# interfaces.net
KiCad netlist of a schematic drawn in Altium Designer
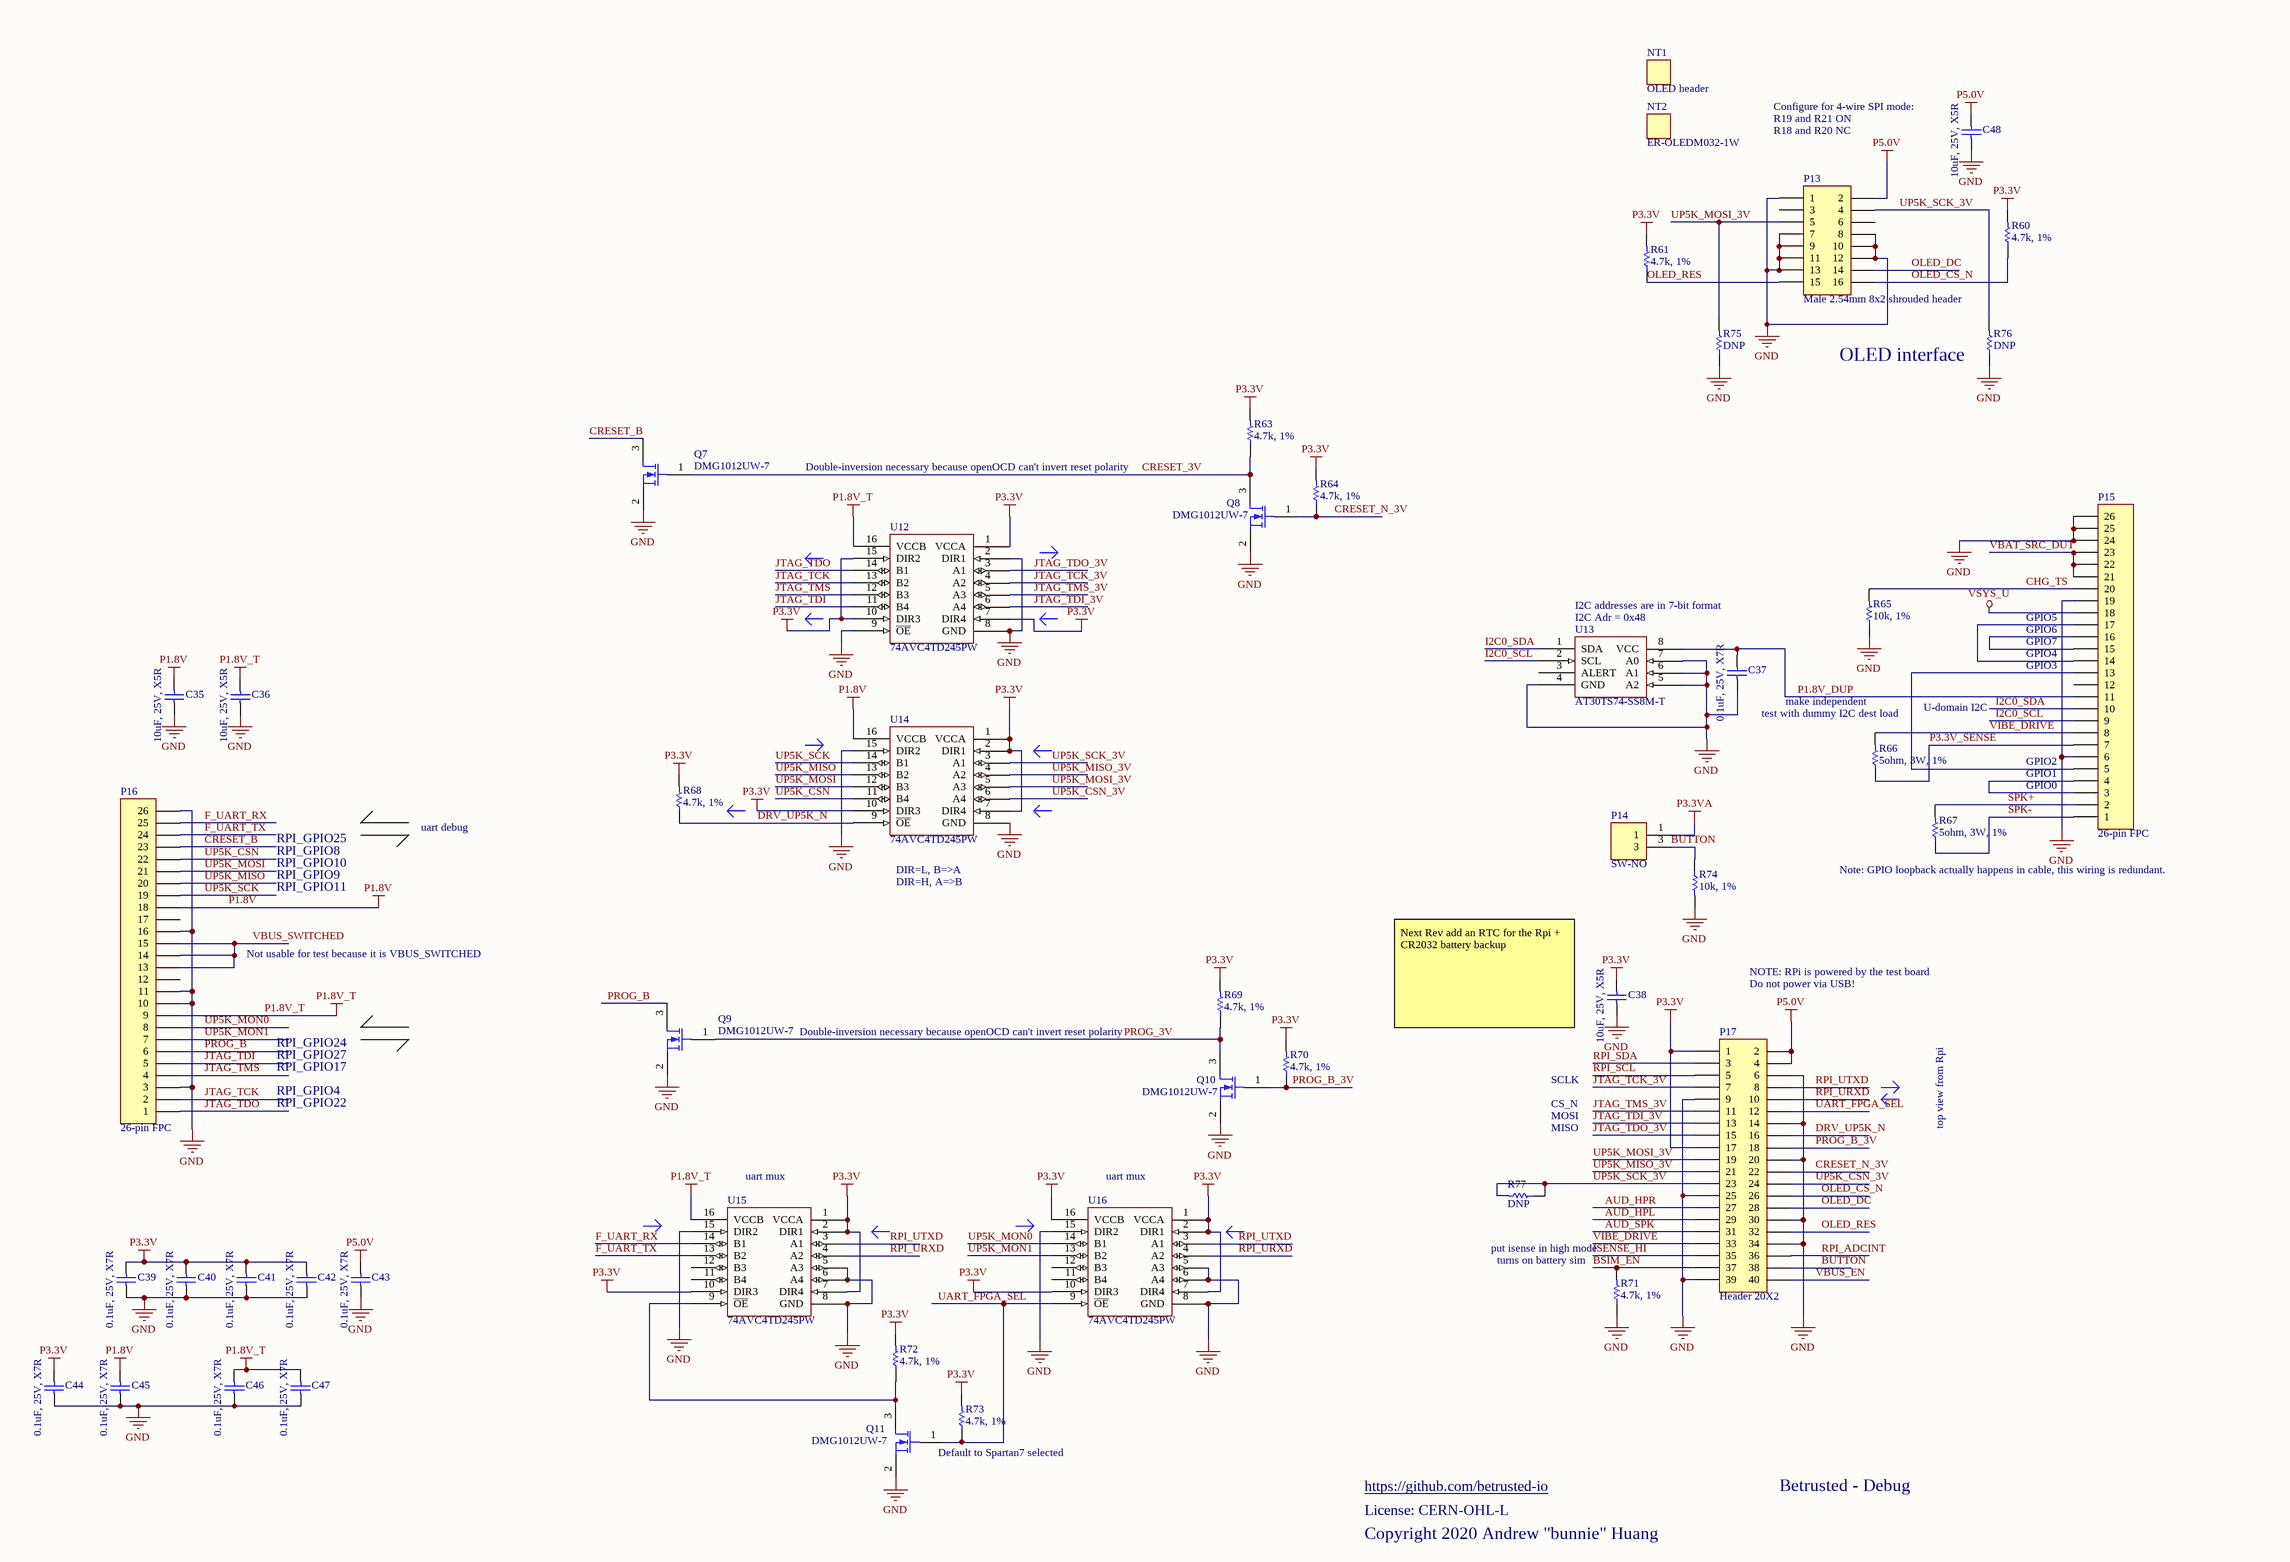
[diagram p0: interfaces.SchDoc]

(export (version "E")
  (design (tool "Eeschema 10.0.6"))
  (components
    (comp (ref "C35")
      (value "10uF, 25V, X5R")
      (footprint "B_CAP0805")
      (description "Capacitor (Semiconductor SIM Model)")
      (fields (field (name "MPN") "GRM21BR61E106KA73L"))
      (libsource (lib "Miscellaneous Devices") (part "Cap Semi"))
    )
    (comp (ref "C36")
      (value "10uF, 25V, X5R")
      (footprint "B_CAP0805")
      (description "Capacitor (Semiconductor SIM Model)")
      (fields (field (name "MPN") "GRM21BR61E106KA73L"))
      (libsource (lib "Miscellaneous Devices") (part "Cap Semi"))
    )
    (comp (ref "C37")
      (value "0.1uF, 25V, X7R")
      (footprint "B_CAP0603")
      (description "Capacitor (Semiconductor SIM Model)")
      (fields (field (name "MPN") "CC0603KRX7R8BB104"))
      (libsource (lib "Miscellaneous Devices") (part "Cap Semi"))
    )
    (comp (ref "C38")
      (value "10uF, 25V, X5R")
      (footprint "B_CAP0805")
      (description "Capacitor (Semiconductor SIM Model)")
      (fields (field (name "MPN") "GRM21BR61E106KA73L"))
      (libsource (lib "Miscellaneous Devices") (part "Cap Semi"))
    )
    (comp (ref "C39")
      (value "0.1uF, 25V, X7R")
      (footprint "B_CAP0603")
      (description "Capacitor (Semiconductor SIM Model)")
      (fields (field (name "MPN") "CC0603KRX7R8BB104"))
      (libsource (lib "Miscellaneous Devices") (part "Cap Semi"))
    )
    (comp (ref "C40")
      (value "0.1uF, 25V, X7R")
      (footprint "B_CAP0603")
      (description "Capacitor (Semiconductor SIM Model)")
      (fields (field (name "MPN") "CC0603KRX7R8BB104"))
      (libsource (lib "Miscellaneous Devices") (part "Cap Semi"))
    )
    (comp (ref "C41")
      (value "0.1uF, 25V, X7R")
      (footprint "B_CAP0603")
      (description "Capacitor (Semiconductor SIM Model)")
      (fields (field (name "MPN") "CC0603KRX7R8BB104"))
      (libsource (lib "Miscellaneous Devices") (part "Cap Semi"))
    )
    (comp (ref "C42")
      (value "0.1uF, 25V, X7R")
      (footprint "B_CAP0603")
      (description "Capacitor (Semiconductor SIM Model)")
      (fields (field (name "MPN") "CC0603KRX7R8BB104"))
      (libsource (lib "Miscellaneous Devices") (part "Cap Semi"))
    )
    (comp (ref "C43")
      (value "0.1uF, 25V, X7R")
      (footprint "B_CAP0603")
      (description "Capacitor (Semiconductor SIM Model)")
      (fields (field (name "MPN") "CC0603KRX7R8BB104"))
      (libsource (lib "Miscellaneous Devices") (part "Cap Semi"))
    )
    (comp (ref "C44")
      (value "0.1uF, 25V, X7R")
      (footprint "B_CAP0603")
      (description "Capacitor (Semiconductor SIM Model)")
      (fields (field (name "MPN") "CC0603KRX7R8BB104"))
      (libsource (lib "Miscellaneous Devices") (part "Cap Semi"))
    )
    (comp (ref "C45")
      (value "0.1uF, 25V, X7R")
      (footprint "B_CAP0603")
      (description "Capacitor (Semiconductor SIM Model)")
      (fields (field (name "MPN") "CC0603KRX7R8BB104"))
      (libsource (lib "Miscellaneous Devices") (part "Cap Semi"))
    )
    (comp (ref "C46")
      (value "0.1uF, 25V, X7R")
      (footprint "B_CAP0603")
      (description "Capacitor (Semiconductor SIM Model)")
      (fields (field (name "MPN") "CC0603KRX7R8BB104"))
      (libsource (lib "Miscellaneous Devices") (part "Cap Semi"))
    )
    (comp (ref "C47")
      (value "0.1uF, 25V, X7R")
      (footprint "B_CAP0603")
      (description "Capacitor (Semiconductor SIM Model)")
      (fields (field (name "MPN") "CC0603KRX7R8BB104"))
      (libsource (lib "Miscellaneous Devices") (part "Cap Semi"))
    )
    (comp (ref "C48")
      (value "10uF, 25V, X5R")
      (footprint "B_CAP0805")
      (description "Capacitor (Semiconductor SIM Model)")
      (fields (field (name "MPN") "GRM21BR61E106KA73L"))
      (libsource (lib "Miscellaneous Devices") (part "Cap Semi"))
    )
    (comp (ref "NT1")
      (value "OLED header")
      (description "Placeholder for non-board BOM items")
      (fields (field (name "MPN") "PPPC082LFBN-RC"))
      (libsource (lib "commonsch") (part "NOTE"))
    )
    (comp (ref "NT2")
      (value "ER-OLEDM032-1W")
      (description "Placeholder for non-board BOM items")
      (libsource (lib "commonsch") (part "NOTE"))
    )
    (comp (ref "P13")
      (value "Male 2.54mm 8x2 shrouded header")
      (footprint "ER_OLED_M032_1")
      (description "Header, 8-Pin, Dual row, shrouded")
      (fields (field (name "MPN") "PRPC008DAAN-RC") (field (name "PUBLISHER") "Altium Limited"))
      (libsource (lib "Miscellaneous Connectors") (part "Header 8X2"))
    )
    (comp (ref "P14")
      (value "SW-NO")
      (footprint "CK_KS11R22CQD")
      (description "Header, 2-Pin")
      (fields (field (name "PUBLISHER") "Altium Limited"))
      (libsource (lib "Miscellaneous Connectors") (part "Header 2"))
    )
    (comp (ref "P15")
      (value "26-pin FPC")
      (footprint "HRS_FH34SRJ-26S-0.5SH(50)")
      (description "26 Pin FPC header")
      (fields (field (name "MPN") "FH34SRJ-26S-0.5SH(99)"))
      (libsource (lib "") (part "FPC-26_1"))
    )
    (comp (ref "P16")
      (value "26-pin FPC")
      (footprint "HRS_FH34SRJ-26S-0.5SH(50)")
      (description "26 Pin FPC header")
      (fields (field (name "MPN") "FH34SRJ-26S-0.5SH(99)"))
      (libsource (lib "commonsch-new") (part "FPC-26"))
    )
    (comp (ref "P17")
      (value "Header 20X2")
      (footprint "SAMTEC_SSW-120-01-F-D")
      (description "Header, 20-Pin, Dual row")
      (fields (field (name "MPN") "P-SSW-120-01-F-D") (field (name "PUBLISHER") "Altium Limited"))
      (libsource (lib "Miscellaneous Connectors") (part "Header 20X2"))
    )
    (comp (ref "Q7")
      (value "DMG1012UW-7")
      (footprint "SOT323-3AN")
      (description "N-Channel MOSFET")
      (fields (field (name "PUBLISHER") "Altium Limited"))
      (libsource (lib "Miscellaneous Devices") (part "MOSFET-N"))
    )
    (comp (ref "Q8")
      (value "DMG1012UW-7")
      (footprint "SOT323-3AN")
      (description "N-Channel MOSFET")
      (fields (field (name "PUBLISHER") "Altium Limited"))
      (libsource (lib "Miscellaneous Devices") (part "MOSFET-N"))
    )
    (comp (ref "Q9")
      (value "DMG1012UW-7")
      (footprint "SOT323-3AN")
      (description "N-Channel MOSFET")
      (fields (field (name "PUBLISHER") "Altium Limited"))
      (libsource (lib "Miscellaneous Devices") (part "MOSFET-N"))
    )
    (comp (ref "Q10")
      (value "DMG1012UW-7")
      (footprint "SOT323-3AN")
      (description "N-Channel MOSFET")
      (fields (field (name "PUBLISHER") "Altium Limited"))
      (libsource (lib "Miscellaneous Devices") (part "MOSFET-N"))
    )
    (comp (ref "Q11")
      (value "DMG1012UW-7")
      (footprint "SOT323-3AN")
      (description "N-Channel MOSFET")
      (fields (field (name "PUBLISHER") "Altium Limited"))
      (libsource (lib "Miscellaneous Devices") (part "MOSFET-N"))
    )
    (comp (ref "R60")
      (value "4.7k, 1%")
      (footprint "B_RES0603")
      (description "Resistor")
      (fields (field (name "MPN") "RC0603FR-074K7L"))
      (libsource (lib "Miscellaneous Devices") (part "Res1"))
    )
    (comp (ref "R61")
      (value "4.7k, 1%")
      (footprint "B_RES0603")
      (description "Resistor")
      (fields (field (name "MPN") "RC0603FR-074K7L"))
      (libsource (lib "Miscellaneous Devices") (part "Res1"))
    )
    (comp (ref "R63")
      (value "4.7k, 1%")
      (footprint "B_RES0603")
      (description "Resistor")
      (fields (field (name "MPN") "RC0603FR-074K7L"))
      (libsource (lib "Miscellaneous Devices") (part "Res1"))
    )
    (comp (ref "R64")
      (value "4.7k, 1%")
      (footprint "B_RES0603")
      (description "Resistor")
      (fields (field (name "MPN") "RC0603FR-074K7L"))
      (libsource (lib "Miscellaneous Devices") (part "Res1"))
    )
    (comp (ref "R65")
      (value "10k, 1%")
      (footprint "B_RES0603")
      (description "Resistor")
      (fields (field (name "MPN") "RC0603FR-0710KL"))
      (libsource (lib "Miscellaneous Devices") (part "Res1"))
    )
    (comp (ref "R66")
      (value "5ohm, 3W, 1%")
      (footprint "OHMITE_43_3W")
      (description "Resistor")
      (fields (field (name "MPN") "43F5R0E"))
      (libsource (lib "Miscellaneous Devices") (part "Res1"))
    )
    (comp (ref "R67")
      (value "5ohm, 3W, 1%")
      (footprint "OHMITE_43_3W")
      (description "Resistor")
      (fields (field (name "MPN") "43F5R0E"))
      (libsource (lib "Miscellaneous Devices") (part "Res1"))
    )
    (comp (ref "R68")
      (value "4.7k, 1%")
      (footprint "B_RES0603")
      (description "Resistor")
      (fields (field (name "MPN") "RC0603FR-074K7L"))
      (libsource (lib "Miscellaneous Devices") (part "Res1"))
    )
    (comp (ref "R69")
      (value "4.7k, 1%")
      (footprint "B_RES0603")
      (description "Resistor")
      (fields (field (name "MPN") "RC0603FR-074K7L"))
      (libsource (lib "Miscellaneous Devices") (part "Res1"))
    )
    (comp (ref "R70")
      (value "4.7k, 1%")
      (footprint "B_RES0603")
      (description "Resistor")
      (fields (field (name "MPN") "RC0603FR-074K7L"))
      (libsource (lib "Miscellaneous Devices") (part "Res1"))
    )
    (comp (ref "R71")
      (value "4.7k, 1%")
      (footprint "B_RES0603")
      (description "Resistor")
      (fields (field (name "MPN") "RC0603FR-074K7L"))
      (libsource (lib "Miscellaneous Devices") (part "Res1"))
    )
    (comp (ref "R72")
      (value "4.7k, 1%")
      (footprint "B_RES0603")
      (description "Resistor")
      (fields (field (name "MPN") "RC0603FR-074K7L"))
      (libsource (lib "Miscellaneous Devices") (part "Res1"))
    )
    (comp (ref "R73")
      (value "4.7k, 1%")
      (footprint "B_RES0603")
      (description "Resistor")
      (fields (field (name "MPN") "RC0603FR-074K7L"))
      (libsource (lib "Miscellaneous Devices") (part "Res1"))
    )
    (comp (ref "R74")
      (value "10k, 1%")
      (footprint "B_RES0603")
      (description "Resistor")
      (fields (field (name "MPN") "RC0603FR-0710KL"))
      (libsource (lib "Miscellaneous Devices") (part "Res1"))
    )
    (comp (ref "R75")
      (value "DNP")
      (footprint "B_RES0603")
      (description "Resistor")
      (fields (field (name "MPN") "ANY"))
      (libsource (lib "Miscellaneous Devices") (part "Res1"))
    )
    (comp (ref "R76")
      (value "DNP")
      (footprint "B_RES0603")
      (description "Resistor")
      (fields (field (name "MPN") "ANY"))
      (libsource (lib "Miscellaneous Devices") (part "Res1"))
    )
    (comp (ref "R77")
      (value "DNP")
      (footprint "B_RES0603")
      (description "Resistor")
      (fields (field (name "MPN") "ANY"))
      (libsource (lib "Miscellaneous Devices") (part "Res1"))
    )
    (comp (ref "U12")
      (value "74AVC4TD245PW")
      (footprint "TSOP65P640-16AN")
      (description "4-bit dual supply translating transceiver with configurable voltage translation; 3-state")
      (libsource (lib "commonsch-new") (part "74AVC4TD245"))
    )
    (comp (ref "U13")
      (value "AT30TS74-SS8M-T")
      (footprint "SOIC127P600-8AN")
      (description "9- to 12-bit Selectable, ±1.0°C Accurate Digital Temperature Sensor")
      (libsource (lib "commonsch-new") (part "AT30TS74-SS8M-T"))
    )
    (comp (ref "U14")
      (value "74AVC4TD245PW")
      (footprint "TSOP65P640-16AN")
      (description "4-bit dual supply translating transceiver with configurable voltage translation; 3-state")
      (libsource (lib "commonsch-new") (part "74AVC4TD245"))
    )
    (comp (ref "U15")
      (value "74AVC4TD245PW")
      (footprint "TSOP65P640-16AN")
      (description "4-bit dual supply translating transceiver with configurable voltage translation; 3-state")
      (libsource (lib "commonsch-new") (part "74AVC4TD245"))
    )
    (comp (ref "U16")
      (value "74AVC4TD245PW")
      (footprint "TSOP65P640-16AN")
      (description "4-bit dual supply translating transceiver with configurable voltage translation; 3-state")
      (libsource (lib "commonsch-new") (part "74AVC4TD245"))
    )
  )
  (nets
    (net (code "1") (name "/AUD_HPL") (class "Default")
      (node (ref "P17") (pin "29") (pinfunction "29_29") (pintype "passive"))
    )
    (net (code "2") (name "/AUD_HPR") (class "Default")
      (node (ref "P17") (pin "27") (pinfunction "27_27") (pintype "passive"))
    )
    (net (code "3") (name "/AUD_SPK") (class "Default")
      (node (ref "P17") (pin "31") (pinfunction "31_31") (pintype "passive"))
    )
    (net (code "4") (name "/BSIM_EN") (class "Default")
      (node (ref "P17") (pin "37") (pinfunction "37_37") (pintype "passive"))
      (node (ref "R71") (pin "2") (pinfunction "2_2") (pintype "passive"))
    )
    (net (code "5") (name "/BUTTON") (class "Default")
      (node (ref "P14") (pin "3") (pinfunction "3_3") (pintype "passive"))
      (node (ref "P17") (pin "38") (pinfunction "38_38") (pintype "passive"))
      (node (ref "R74") (pin "1") (pinfunction "1_1") (pintype "passive"))
    )
    (net (code "6") (name "/CHG_TS") (class "Default")
      (node (ref "P15") (pin "20") (pinfunction "20_20") (pintype "passive"))
      (node (ref "R65") (pin "2") (pinfunction "2_2") (pintype "passive"))
    )
    (net (code "7") (name "/CRESET_3V") (class "Default")
      (node (ref "Q7") (pin "1") (pinfunction "G_1") (pintype "passive"))
      (node (ref "Q8") (pin "3") (pinfunction "D_3") (pintype "passive"))
      (node (ref "R63") (pin "1") (pinfunction "1_1") (pintype "passive"))
    )
    (net (code "8") (name "/CRESET_B") (class "Default")
      (node (ref "P16") (pin "23") (pinfunction "23_23") (pintype "passive"))
      (node (ref "Q7") (pin "3") (pinfunction "D_3") (pintype "passive"))
    )
    (net (code "9") (name "/CRESET_N_3V") (class "Default")
      (node (ref "P17") (pin "22") (pinfunction "22_22") (pintype "passive"))
      (node (ref "Q8") (pin "1") (pinfunction "G_1") (pintype "passive"))
      (node (ref "R64") (pin "1") (pinfunction "1_1") (pintype "passive"))
    )
    (net (code "10") (name "/DRV_UP5K_N") (class "Default")
      (node (ref "P17") (pin "16") (pinfunction "16_16") (pintype "passive"))
      (node (ref "R68") (pin "1") (pinfunction "1_1") (pintype "passive"))
      (node (ref "U14") (pin "9") (pinfunction "~{OE}_9") (pintype "input"))
    )
    (net (code "11") (name "/F_UART_RX") (class "Default")
      (node (ref "P16") (pin "25") (pinfunction "25_25") (pintype "passive"))
      (node (ref "U15") (pin "14") (pinfunction "B1_14") (pintype "bidirectional"))
    )
    (net (code "12") (name "/F_UART_TX") (class "Default")
      (node (ref "P16") (pin "24") (pinfunction "24_24") (pintype "passive"))
      (node (ref "U15") (pin "13") (pinfunction "B2_13") (pintype "bidirectional"))
    )
    (net (code "13") (name "/I2C0_SCL") (class "Default")
      (node (ref "P15") (pin "9") (pinfunction "9_9") (pintype "passive"))
      (node (ref "U13") (pin "2") (pinfunction "SCL_2") (pintype "input"))
    )
    (net (code "14") (name "/I2C0_SDA") (class "Default")
      (node (ref "P15") (pin "10") (pinfunction "10_10") (pintype "passive"))
      (node (ref "U13") (pin "1") (pinfunction "SDA_1") (pintype "open_collector"))
    )
    (net (code "15") (name "/ISENSE_HI") (class "Default")
      (node (ref "P17") (pin "35") (pinfunction "35_35") (pintype "passive"))
    )
    (net (code "16") (name "/JTAG_TCK") (class "Default")
      (node (ref "P16") (pin "2") (pinfunction "2_2") (pintype "passive"))
      (node (ref "U12") (pin "13") (pinfunction "B2_13") (pintype "bidirectional"))
    )
    (net (code "17") (name "/JTAG_TCK_3V") (class "Default")
      (node (ref "P17") (pin "7") (pinfunction "7_7") (pintype "passive"))
      (node (ref "U12") (pin "4") (pinfunction "A2_4") (pintype "bidirectional"))
    )
    (net (code "18") (name "/JTAG_TDI") (class "Default")
      (node (ref "P16") (pin "5") (pinfunction "5_5") (pintype "passive"))
      (node (ref "U12") (pin "11") (pinfunction "B4_11") (pintype "bidirectional"))
    )
    (net (code "19") (name "/JTAG_TDI_3V") (class "Default")
      (node (ref "P17") (pin "13") (pinfunction "13_13") (pintype "passive"))
      (node (ref "U12") (pin "6") (pinfunction "A4_6") (pintype "bidirectional"))
    )
    (net (code "20") (name "/JTAG_TDO") (class "Default")
      (node (ref "P16") (pin "1") (pinfunction "1_1") (pintype "passive"))
      (node (ref "U12") (pin "14") (pinfunction "B1_14") (pintype "bidirectional"))
    )
    (net (code "21") (name "/JTAG_TDO_3V") (class "Default")
      (node (ref "P17") (pin "15") (pinfunction "15_15") (pintype "passive"))
      (node (ref "U12") (pin "3") (pinfunction "A1_3") (pintype "bidirectional"))
    )
    (net (code "22") (name "/JTAG_TMS") (class "Default")
      (node (ref "P16") (pin "4") (pinfunction "4_4") (pintype "passive"))
      (node (ref "U12") (pin "12") (pinfunction "B3_12") (pintype "bidirectional"))
    )
    (net (code "23") (name "/JTAG_TMS_3V") (class "Default")
      (node (ref "P17") (pin "11") (pinfunction "11_11") (pintype "passive"))
      (node (ref "U12") (pin "5") (pinfunction "A3_5") (pintype "bidirectional"))
    )
    (net (code "24") (name "/OLED_CS_N") (class "Default")
      (node (ref "P13") (pin "16") (pinfunction "16_16") (pintype "passive"))
      (node (ref "P17") (pin "26") (pinfunction "26_26") (pintype "passive"))
      (node (ref "R60") (pin "1") (pinfunction "1_1") (pintype "passive"))
    )
    (net (code "25") (name "/OLED_DC") (class "Default")
      (node (ref "P13") (pin "14") (pinfunction "14_14") (pintype "passive"))
      (node (ref "P17") (pin "28") (pinfunction "28_28") (pintype "passive"))
    )
    (net (code "26") (name "/OLED_RES") (class "Default")
      (node (ref "P13") (pin "15") (pinfunction "15_15") (pintype "passive"))
      (node (ref "P17") (pin "32") (pinfunction "32_32") (pintype "passive"))
      (node (ref "R61") (pin "1") (pinfunction "1_1") (pintype "passive"))
    )
    (net (code "27") (name "/P1.8V_DUP") (class "Default")
      (node (ref "C37") (pin "1") (pinfunction "1_1") (pintype "passive"))
      (node (ref "P15") (pin "11") (pinfunction "11_11") (pintype "passive"))
      (node (ref "U13") (pin "8") (pinfunction "VCC_8") (pintype "power_in"))
    )
    (net (code "28") (name "/P3.3V_SENSE") (class "Default")
      (node (ref "P15") (pin "7") (pinfunction "7_7") (pintype "passive"))
      (node (ref "R66") (pin "1") (pinfunction "1_1") (pintype "passive"))
    )
    (net (code "29") (name "/PROG_3V") (class "Default")
      (node (ref "Q10") (pin "3") (pinfunction "D_3") (pintype "passive"))
      (node (ref "Q9") (pin "1") (pinfunction "G_1") (pintype "passive"))
      (node (ref "R69") (pin "1") (pinfunction "1_1") (pintype "passive"))
    )
    (net (code "30") (name "/PROG_B") (class "Default")
      (node (ref "P16") (pin "6") (pinfunction "6_6") (pintype "passive"))
      (node (ref "Q9") (pin "3") (pinfunction "D_3") (pintype "passive"))
    )
    (net (code "31") (name "/PROG_B_3V") (class "Default")
      (node (ref "P17") (pin "18") (pinfunction "18_18") (pintype "passive"))
      (node (ref "Q10") (pin "1") (pinfunction "G_1") (pintype "passive"))
      (node (ref "R70") (pin "1") (pinfunction "1_1") (pintype "passive"))
    )
    (net (code "32") (name "/RPI_ADCINT") (class "Default")
      (node (ref "P17") (pin "36") (pinfunction "36_36") (pintype "passive"))
    )
    (net (code "33") (name "/RPI_SCL") (class "Default")
      (node (ref "P17") (pin "5") (pinfunction "5_5") (pintype "passive"))
    )
    (net (code "34") (name "/RPI_SDA") (class "Default")
      (node (ref "P17") (pin "3") (pinfunction "3_3") (pintype "passive"))
    )
    (net (code "35") (name "/RPI_URXD") (class "Default")
      (node (ref "P17") (pin "10") (pinfunction "10_10") (pintype "passive"))
      (node (ref "U15") (pin "4") (pinfunction "A2_4") (pintype "bidirectional"))
      (node (ref "U16") (pin "4") (pinfunction "A2_4") (pintype "bidirectional"))
    )
    (net (code "36") (name "/RPI_UTXD") (class "Default")
      (node (ref "P17") (pin "8") (pinfunction "8_8") (pintype "passive"))
      (node (ref "U15") (pin "3") (pinfunction "A1_3") (pintype "bidirectional"))
      (node (ref "U16") (pin "3") (pinfunction "A1_3") (pintype "bidirectional"))
    )
    (net (code "37") (name "/SPK+") (class "Default")
      (node (ref "P15") (pin "2") (pinfunction "2_2") (pintype "passive"))
      (node (ref "R67") (pin "2") (pinfunction "2_2") (pintype "passive"))
    )
    (net (code "38") (name "/SPK-") (class "Default")
      (node (ref "P15") (pin "1") (pinfunction "1_1") (pintype "passive"))
      (node (ref "R67") (pin "1") (pinfunction "1_1") (pintype "passive"))
    )
    (net (code "39") (name "/UART_FPGA_SEL") (class "Default")
      (node (ref "P17") (pin "12") (pinfunction "12_12") (pintype "passive"))
      (node (ref "Q11") (pin "1") (pinfunction "G_1") (pintype "passive"))
      (node (ref "R73") (pin "1") (pinfunction "1_1") (pintype "passive"))
      (node (ref "U16") (pin "9") (pinfunction "~{OE}_9") (pintype "input"))
    )
    (net (code "40") (name "/UP5K_CSN") (class "Default")
      (node (ref "P16") (pin "22") (pinfunction "22_22") (pintype "passive"))
      (node (ref "U14") (pin "11") (pinfunction "B4_11") (pintype "bidirectional"))
    )
    (net (code "41") (name "/UP5K_CSN_3V") (class "Default")
      (node (ref "P17") (pin "24") (pinfunction "24_24") (pintype "passive"))
      (node (ref "U14") (pin "6") (pinfunction "A4_6") (pintype "bidirectional"))
    )
    (net (code "42") (name "/UP5K_MISO") (class "Default")
      (node (ref "P16") (pin "20") (pinfunction "20_20") (pintype "passive"))
      (node (ref "U14") (pin "13") (pinfunction "B2_13") (pintype "bidirectional"))
    )
    (net (code "43") (name "/UP5K_MISO_3V") (class "Default")
      (node (ref "P17") (pin "21") (pinfunction "21_21") (pintype "passive"))
      (node (ref "U14") (pin "4") (pinfunction "A2_4") (pintype "bidirectional"))
    )
    (net (code "44") (name "/UP5K_MON0") (class "Default")
      (node (ref "P16") (pin "8") (pinfunction "8_8") (pintype "passive"))
      (node (ref "U16") (pin "14") (pinfunction "B1_14") (pintype "bidirectional"))
    )
    (net (code "45") (name "/UP5K_MON1") (class "Default")
      (node (ref "P16") (pin "7") (pinfunction "7_7") (pintype "passive"))
      (node (ref "U16") (pin "13") (pinfunction "B2_13") (pintype "bidirectional"))
    )
    (net (code "46") (name "/UP5K_MOSI") (class "Default")
      (node (ref "P16") (pin "21") (pinfunction "21_21") (pintype "passive"))
      (node (ref "U14") (pin "12") (pinfunction "B3_12") (pintype "bidirectional"))
    )
    (net (code "47") (name "/UP5K_MOSI_3V") (class "Default")
      (node (ref "P13") (pin "5") (pinfunction "5_5") (pintype "passive"))
      (node (ref "P17") (pin "19") (pinfunction "19_19") (pintype "passive"))
      (node (ref "R75") (pin "2") (pinfunction "2_2") (pintype "passive"))
      (node (ref "U14") (pin "5") (pinfunction "A3_5") (pintype "bidirectional"))
    )
    (net (code "48") (name "/UP5K_SCK") (class "Default")
      (node (ref "P16") (pin "19") (pinfunction "19_19") (pintype "passive"))
      (node (ref "U14") (pin "14") (pinfunction "B1_14") (pintype "bidirectional"))
    )
    (net (code "49") (name "/UP5K_SCK_3V") (class "Default")
      (node (ref "P13") (pin "4") (pinfunction "4_4") (pintype "passive"))
      (node (ref "P17") (pin "23") (pinfunction "23_23") (pintype "passive"))
      (node (ref "R76") (pin "2") (pinfunction "2_2") (pintype "passive"))
      (node (ref "R77") (pin "1") (pinfunction "1_1") (pintype "passive"))
      (node (ref "R77") (pin "2") (pinfunction "2_2") (pintype "passive"))
      (node (ref "U14") (pin "3") (pinfunction "A1_3") (pintype "bidirectional"))
    )
    (net (code "50") (name "/VBAT_SRC_DUT") (class "Default")
      (node (ref "P15") (pin "21") (pinfunction "21_21") (pintype "passive"))
      (node (ref "P15") (pin "22") (pinfunction "22_22") (pintype "passive"))
      (node (ref "P15") (pin "23") (pinfunction "23_23") (pintype "passive"))
    )
    (net (code "51") (name "/VBUS_EN") (class "Default")
      (node (ref "P17") (pin "40") (pinfunction "40_40") (pintype "passive"))
    )
    (net (code "52") (name "/VBUS_SWITCHED") (class "Default")
      (node (ref "P16") (pin "13") (pinfunction "13_13") (pintype "passive"))
      (node (ref "P16") (pin "14") (pinfunction "14_14") (pintype "passive"))
      (node (ref "P16") (pin "15") (pinfunction "15_15") (pintype "passive"))
    )
    (net (code "53") (name "/VIBE_DRIVE") (class "Default")
      (node (ref "P15") (pin "8") (pinfunction "8_8") (pintype "passive"))
      (node (ref "P17") (pin "33") (pinfunction "33_33") (pintype "passive"))
      (node (ref "R66") (pin "2") (pinfunction "2_2") (pintype "passive"))
    )
    (net (code "54") (name "GND") (class "Default")
      (node (ref "C35") (pin "2") (pinfunction "2_2") (pintype "passive"))
      (node (ref "C36") (pin "2") (pinfunction "2_2") (pintype "passive"))
      (node (ref "C37") (pin "2") (pinfunction "2_2") (pintype "passive"))
      (node (ref "C38") (pin "2") (pinfunction "2_2") (pintype "passive"))
      (node (ref "C39") (pin "2") (pinfunction "2_2") (pintype "passive"))
      (node (ref "C40") (pin "2") (pinfunction "2_2") (pintype "passive"))
      (node (ref "C41") (pin "2") (pinfunction "2_2") (pintype "passive"))
      (node (ref "C42") (pin "2") (pinfunction "2_2") (pintype "passive"))
      (node (ref "C43") (pin "2") (pinfunction "2_2") (pintype "passive"))
      (node (ref "C44") (pin "2") (pinfunction "2_2") (pintype "passive"))
      (node (ref "C45") (pin "2") (pinfunction "2_2") (pintype "passive"))
      (node (ref "C46") (pin "2") (pinfunction "2_2") (pintype "passive"))
      (node (ref "C47") (pin "2") (pinfunction "2_2") (pintype "passive"))
      (node (ref "C48") (pin "2") (pinfunction "2_2") (pintype "passive"))
      (node (ref "P13") (pin "1") (pinfunction "1_1") (pintype "passive"))
      (node (ref "P13") (pin "10") (pinfunction "10_10") (pintype "passive"))
      (node (ref "P13") (pin "11") (pinfunction "11_11") (pintype "passive"))
      (node (ref "P13") (pin "12") (pinfunction "12_12") (pintype "passive"))
      (node (ref "P13") (pin "13") (pinfunction "13_13") (pintype "passive"))
      (node (ref "P13") (pin "7") (pinfunction "7_7") (pintype "passive"))
      (node (ref "P13") (pin "8") (pinfunction "8_8") (pintype "passive"))
      (node (ref "P13") (pin "9") (pinfunction "9_9") (pintype "passive"))
      (node (ref "P15") (pin "19") (pinfunction "19_19") (pintype "passive"))
      (node (ref "P15") (pin "24") (pinfunction "24_24") (pintype "passive"))
      (node (ref "P15") (pin "25") (pinfunction "25_25") (pintype "passive"))
      (node (ref "P15") (pin "26") (pinfunction "26_26") (pintype "passive"))
      (node (ref "P15") (pin "6") (pinfunction "6_6") (pintype "passive"))
      (node (ref "P16") (pin "10") (pinfunction "10_10") (pintype "passive"))
      (node (ref "P16") (pin "11") (pinfunction "11_11") (pintype "passive"))
      (node (ref "P16") (pin "16") (pinfunction "16_16") (pintype "passive"))
      (node (ref "P16") (pin "26") (pinfunction "26_26") (pintype "passive"))
      (node (ref "P16") (pin "3") (pinfunction "3_3") (pintype "passive"))
      (node (ref "P17") (pin "14") (pinfunction "14_14") (pintype "passive"))
      (node (ref "P17") (pin "20") (pinfunction "20_20") (pintype "passive"))
      (node (ref "P17") (pin "25") (pinfunction "25_25") (pintype "passive"))
      (node (ref "P17") (pin "30") (pinfunction "30_30") (pintype "passive"))
      (node (ref "P17") (pin "34") (pinfunction "34_34") (pintype "passive"))
      (node (ref "P17") (pin "39") (pinfunction "39_39") (pintype "passive"))
      (node (ref "P17") (pin "6") (pinfunction "6_6") (pintype "passive"))
      (node (ref "P17") (pin "9") (pinfunction "9_9") (pintype "passive"))
      (node (ref "Q10") (pin "2") (pinfunction "S_2") (pintype "passive"))
      (node (ref "Q11") (pin "2") (pinfunction "S_2") (pintype "passive"))
      (node (ref "Q7") (pin "2") (pinfunction "S_2") (pintype "passive"))
      (node (ref "Q8") (pin "2") (pinfunction "S_2") (pintype "passive"))
      (node (ref "Q9") (pin "2") (pinfunction "S_2") (pintype "passive"))
      (node (ref "R65") (pin "1") (pinfunction "1_1") (pintype "passive"))
      (node (ref "R71") (pin "1") (pinfunction "1_1") (pintype "passive"))
      (node (ref "R74") (pin "2") (pinfunction "2_2") (pintype "passive"))
      (node (ref "R75") (pin "1") (pinfunction "1_1") (pintype "passive"))
      (node (ref "R76") (pin "1") (pinfunction "1_1") (pintype "passive"))
      (node (ref "U12") (pin "2") (pinfunction "DIR1_2") (pintype "input"))
      (node (ref "U12") (pin "8") (pinfunction "GND_8") (pintype "power_in"))
      (node (ref "U12") (pin "9") (pinfunction "~{OE}_9") (pintype "input"))
      (node (ref "U13") (pin "4") (pinfunction "GND_4") (pintype "power_in"))
      (node (ref "U13") (pin "5") (pinfunction "A2_5") (pintype "input"))
      (node (ref "U13") (pin "6") (pinfunction "A1_6") (pintype "input"))
      (node (ref "U13") (pin "7") (pinfunction "A0_7") (pintype "input"))
      (node (ref "U14") (pin "15") (pinfunction "DIR2_15") (pintype "input"))
      (node (ref "U14") (pin "8") (pinfunction "GND_8") (pintype "power_in"))
      (node (ref "U15") (pin "15") (pinfunction "DIR2_15") (pintype "input"))
      (node (ref "U15") (pin "5") (pinfunction "A3_5") (pintype "bidirectional"))
      (node (ref "U15") (pin "6") (pinfunction "A4_6") (pintype "bidirectional"))
      (node (ref "U15") (pin "8") (pinfunction "GND_8") (pintype "power_in"))
      (node (ref "U16") (pin "15") (pinfunction "DIR2_15") (pintype "input"))
      (node (ref "U16") (pin "5") (pinfunction "A3_5") (pintype "bidirectional"))
      (node (ref "U16") (pin "6") (pinfunction "A4_6") (pintype "bidirectional"))
      (node (ref "U16") (pin "8") (pinfunction "GND_8") (pintype "power_in"))
    )
    (net (code "55") (name "Net-(P15-Pad3)") (class "Default")
      (node (ref "P15") (pin "3") (pinfunction "3_3") (pintype "passive"))
      (node (ref "P15") (pin "4") (pinfunction "4_4") (pintype "passive"))
    )
    (net (code "56") (name "Net-(P15-Pad13)") (class "Default")
      (node (ref "P15") (pin "13") (pinfunction "13_13") (pintype "passive"))
      (node (ref "P15") (pin "5") (pinfunction "5_5") (pintype "passive"))
    )
    (net (code "57") (name "Net-(P15-Pad14)") (class "Default")
      (node (ref "P15") (pin "14") (pinfunction "14_14") (pintype "passive"))
      (node (ref "P15") (pin "17") (pinfunction "17_17") (pintype "passive"))
    )
    (net (code "58") (name "Net-(P15-Pad15)") (class "Default")
      (node (ref "P15") (pin "15") (pinfunction "15_15") (pintype "passive"))
      (node (ref "P15") (pin "16") (pinfunction "16_16") (pintype "passive"))
    )
    (net (code "59") (name "Net-(Q11-D)") (class "Default")
      (node (ref "Q11") (pin "3") (pinfunction "D_3") (pintype "passive"))
      (node (ref "R72") (pin "1") (pinfunction "1_1") (pintype "passive"))
      (node (ref "U15") (pin "9") (pinfunction "~{OE}_9") (pintype "input"))
    )
    (net (code "60") (name "P1.8V") (class "Default")
      (node (ref "C35") (pin "1") (pinfunction "1_1") (pintype "passive"))
      (node (ref "C45") (pin "1") (pinfunction "1_1") (pintype "passive"))
      (node (ref "P16") (pin "18") (pinfunction "18_18") (pintype "passive"))
      (node (ref "U14") (pin "16") (pinfunction "VCCB_16") (pintype "power_in"))
    )
    (net (code "61") (name "P1.8V_T") (class "Default")
      (node (ref "C36") (pin "1") (pinfunction "1_1") (pintype "passive"))
      (node (ref "C46") (pin "1") (pinfunction "1_1") (pintype "passive"))
      (node (ref "C47") (pin "1") (pinfunction "1_1") (pintype "passive"))
      (node (ref "P16") (pin "9") (pinfunction "9_9") (pintype "passive"))
      (node (ref "U12") (pin "16") (pinfunction "VCCB_16") (pintype "power_in"))
      (node (ref "U15") (pin "16") (pinfunction "VCCB_16") (pintype "power_in"))
    )
    (net (code "62") (name "P3.3V") (class "Default")
      (node (ref "C38") (pin "1") (pinfunction "1_1") (pintype "passive"))
      (node (ref "C39") (pin "1") (pinfunction "1_1") (pintype "passive"))
      (node (ref "C40") (pin "1") (pinfunction "1_1") (pintype "passive"))
      (node (ref "C41") (pin "1") (pinfunction "1_1") (pintype "passive"))
      (node (ref "C42") (pin "1") (pinfunction "1_1") (pintype "passive"))
      (node (ref "C44") (pin "1") (pinfunction "1_1") (pintype "passive"))
      (node (ref "P17") (pin "1") (pinfunction "1_1") (pintype "passive"))
      (node (ref "P17") (pin "17") (pinfunction "17_17") (pintype "passive"))
      (node (ref "R60") (pin "2") (pinfunction "2_2") (pintype "passive"))
      (node (ref "R61") (pin "2") (pinfunction "2_2") (pintype "passive"))
      (node (ref "R63") (pin "2") (pinfunction "2_2") (pintype "passive"))
      (node (ref "R64") (pin "2") (pinfunction "2_2") (pintype "passive"))
      (node (ref "R68") (pin "2") (pinfunction "2_2") (pintype "passive"))
      (node (ref "R69") (pin "2") (pinfunction "2_2") (pintype "passive"))
      (node (ref "R70") (pin "2") (pinfunction "2_2") (pintype "passive"))
      (node (ref "R72") (pin "2") (pinfunction "2_2") (pintype "passive"))
      (node (ref "R73") (pin "2") (pinfunction "2_2") (pintype "passive"))
      (node (ref "U12") (pin "1") (pinfunction "VCCA_1") (pintype "power_in"))
      (node (ref "U12") (pin "10") (pinfunction "DIR3_10") (pintype "input"))
      (node (ref "U12") (pin "15") (pinfunction "DIR2_15") (pintype "input"))
      (node (ref "U12") (pin "7") (pinfunction "DIR4_7") (pintype "input"))
      (node (ref "U14") (pin "1") (pinfunction "VCCA_1") (pintype "power_in"))
      (node (ref "U14") (pin "10") (pinfunction "DIR3_10") (pintype "input"))
      (node (ref "U14") (pin "2") (pinfunction "DIR1_2") (pintype "input"))
      (node (ref "U14") (pin "7") (pinfunction "DIR4_7") (pintype "input"))
      (node (ref "U15") (pin "1") (pinfunction "VCCA_1") (pintype "power_in"))
      (node (ref "U15") (pin "10") (pinfunction "DIR3_10") (pintype "input"))
      (node (ref "U15") (pin "2") (pinfunction "DIR1_2") (pintype "input"))
      (node (ref "U15") (pin "7") (pinfunction "DIR4_7") (pintype "input"))
      (node (ref "U16") (pin "1") (pinfunction "VCCA_1") (pintype "power_in"))
      (node (ref "U16") (pin "10") (pinfunction "DIR3_10") (pintype "input"))
      (node (ref "U16") (pin "16") (pinfunction "VCCB_16") (pintype "power_in"))
      (node (ref "U16") (pin "2") (pinfunction "DIR1_2") (pintype "input"))
      (node (ref "U16") (pin "7") (pinfunction "DIR4_7") (pintype "input"))
    )
    (net (code "63") (name "P3.3VA") (class "Default")
      (node (ref "P14") (pin "1") (pinfunction "1_1") (pintype "passive"))
    )
    (net (code "64") (name "P5.0V") (class "Default")
      (node (ref "C43") (pin "1") (pinfunction "1_1") (pintype "passive"))
      (node (ref "C48") (pin "1") (pinfunction "1_1") (pintype "passive"))
      (node (ref "P13") (pin "2") (pinfunction "2_2") (pintype "passive"))
      (node (ref "P17") (pin "2") (pinfunction "2_2") (pintype "passive"))
      (node (ref "P17") (pin "4") (pinfunction "4_4") (pintype "passive"))
    )
    (net (code "65") (name "VSYS_U") (class "Default")
      (node (ref "P15") (pin "18") (pinfunction "18_18") (pintype "passive"))
    )
    (net (code "66") (name "unconnected-(P13-Pad3)") (class "Default")
      (node (ref "P13") (pin "3") (pinfunction "3_3") (pintype "passive"))
    )
    (net (code "67") (name "unconnected-(P13-Pad6)") (class "Default")
      (node (ref "P13") (pin "6") (pinfunction "6_6") (pintype "passive"))
    )
    (net (code "68") (name "unconnected-(P15-Pad12)") (class "Default")
      (node (ref "P15") (pin "12") (pinfunction "12_12") (pintype "passive"))
    )
    (net (code "69") (name "unconnected-(P16-Pad12)") (class "Default")
      (node (ref "P16") (pin "12") (pinfunction "12_12") (pintype "passive"))
    )
    (net (code "70") (name "unconnected-(P16-Pad17)") (class "Default")
      (node (ref "P16") (pin "17") (pinfunction "17_17") (pintype "passive"))
    )
    (net (code "71") (name "unconnected-(U13-ALERT-Pad3)") (class "Default")
      (node (ref "U13") (pin "3") (pinfunction "ALERT_3") (pintype "open_collector"))
    )
    (net (code "72") (name "unconnected-(U15-B3-Pad12)") (class "Default")
      (node (ref "U15") (pin "12") (pinfunction "B3_12") (pintype "bidirectional"))
    )
    (net (code "73") (name "unconnected-(U15-B4-Pad11)") (class "Default")
      (node (ref "U15") (pin "11") (pinfunction "B4_11") (pintype "bidirectional"))
    )
    (net (code "74") (name "unconnected-(U16-B3-Pad12)") (class "Default")
      (node (ref "U16") (pin "12") (pinfunction "B3_12") (pintype "bidirectional"))
    )
    (net (code "75") (name "unconnected-(U16-B4-Pad11)") (class "Default")
      (node (ref "U16") (pin "11") (pinfunction "B4_11") (pintype "bidirectional"))
    )
  )
)
